# Switches.net
KiCad netlist of a schematic drawn in Altium Designer
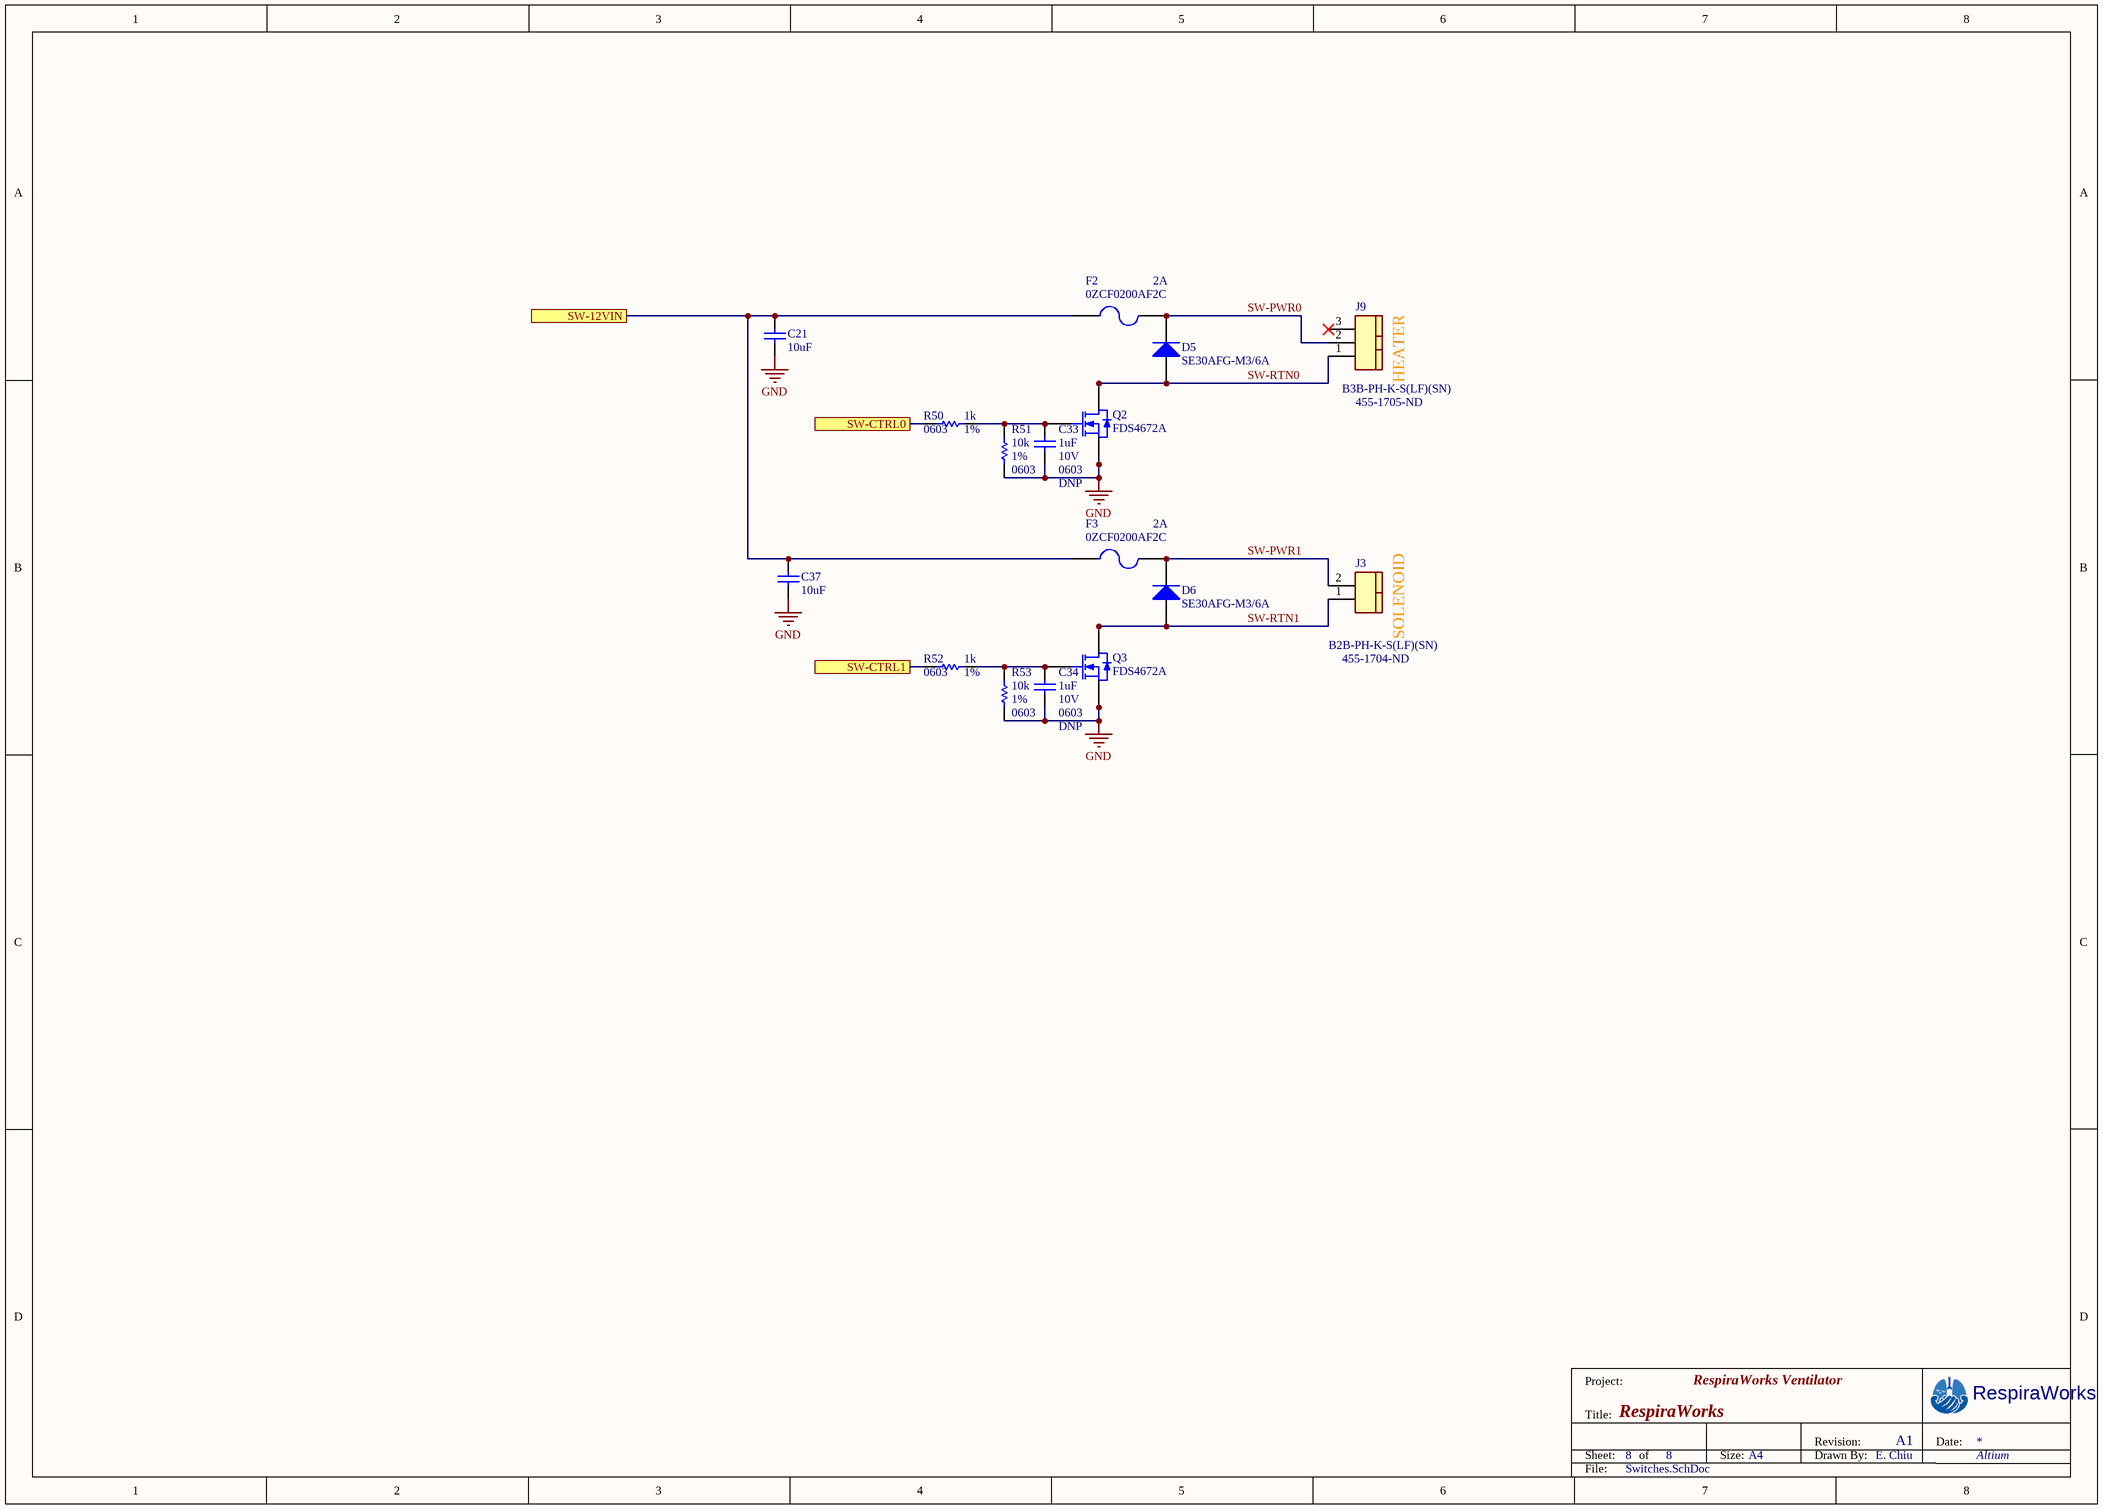
[diagram p0: Switches.SchDoc]

(export (version "E")
  (design (tool "Eeschema 10.0.6"))
  (components
    (comp (ref "C21")
      (value "10uF")
      (footprint "CAP1210")
      (description "Cap 1210")
      (fields (field (name "MANUFACTURER") "Murata") (field (name "VOLTAGE") "25V"))
      (libsource (lib "generic") (part "CAP 1210"))
    )
    (comp (ref "C33")
      (value "1uF")
      (footprint "CAP0603")
      (description "Cap 0603")
      (fields
        (field (name "MANUFACTURER") "Yageo")
        (field (name "VOLTAGE") "10V")
        (field (name "PCB PACKAGE") "0603")
        (field (name "DO NOT POPULATE") "DNP")
        (field (name "Comment") "CAP 0603")
      )
      (libsource (lib "generic") (part "CAP 0603"))
    )
    (comp (ref "C34")
      (value "1uF")
      (footprint "CAP0603")
      (description "Cap 0603")
      (fields
        (field (name "MANUFACTURER") "Yageo")
        (field (name "VOLTAGE") "10V")
        (field (name "PCB PACKAGE") "0603")
        (field (name "DO NOT POPULATE") "DNP")
        (field (name "Comment") "CAP 0603")
      )
      (libsource (lib "generic") (part "CAP 0603"))
    )
    (comp (ref "C37")
      (value "10uF")
      (footprint "CAP1210")
      (description "Cap 1210")
      (fields (field (name "MANUFACTURER") "Murata") (field (name "VOLTAGE") "25V"))
      (libsource (lib "generic") (part "CAP 1210"))
    )
    (comp (ref "D5")
      (value "SE30AFG-M3/6A")
      (footprint "DO-214AC")
      (description "Ultra-Fast Signal Diode, Silicon, 100V, 300mA")
      (fields (field (name "MANUFACTURER") "Vishay") (field (name "MANUFACTURER P/N") "SE30AFG-M3/6A"))
      (libsource (lib "vishay") (part "SE30AFG-M3/6A"))
    )
    (comp (ref "D6")
      (value "SE30AFG-M3/6A")
      (footprint "DO-214AC")
      (description "Ultra-Fast Signal Diode, Silicon, 100V, 300mA")
      (fields (field (name "MANUFACTURER") "Vishay") (field (name "MANUFACTURER P/N") "SE30AFG-M3/6A"))
      (libsource (lib "vishay") (part "SE30AFG-M3/6A"))
    )
    (comp (ref "F2")
      (value "0ZCF0200AF2C")
      (footprint "FUSE2920")
      (description "PTC Fuse, 2A Hold, 24V, 2920 size")
      (fields
        (field (name "MANUFACTURER P/N") "0ZCF0200AF2C")
        (field (name "MANUFACTURER") "Belfuse")
        (field (name "I(HOLD)") "2A")
      )
      (libsource (lib "belfuse") (part "0ZCF0200AF2C"))
    )
    (comp (ref "F3")
      (value "0ZCF0200AF2C")
      (footprint "FUSE2920")
      (description "PTC Fuse, 2A Hold, 24V, 2920 size")
      (fields
        (field (name "MANUFACTURER P/N") "0ZCF0200AF2C")
        (field (name "MANUFACTURER") "Belfuse")
        (field (name "I(HOLD)") "2A")
      )
      (libsource (lib "belfuse") (part "0ZCF0200AF2C"))
    )
    (comp (ref "J3")
      (value "B2B-PH-K-S(LF)(SN)")
      (footprint "JST_B2B-XH-AM")
      (description "CONN HEADER PH TOP 2POS 2MM")
      (fields
        (field (name "MANUFACTURER") "JST Sales America Inc.")
        (field (name "SUPPLIER PART NUMBER 1") "455-1704-ND")
      )
      (libsource (lib "JST XH") (part "B2B-PH-K-S(LF)(SN)"))
    )
    (comp (ref "J9")
      (value "B3B-PH-K-S(LF)(SN)")
      (footprint "JST_B3B-XH-AM")
      (description "CONN HEADER PH TOP 3POS 2MM")
      (fields
        (field (name "MANUFACTURER") "JST Sales America Inc.")
        (field (name "SUPPLIER PART NUMBER 1") "455-1705-ND")
      )
      (libsource (lib "JST XH") (part "B3B-PH-K-S(LF)(SN)"))
    )
    (comp (ref "Q2")
      (value "FDS4672A")
      (footprint "8-SOIC")
      (description "Transistor, BJT NPN, General Purpose 40V")
      (fields (field (name "MANUFACTURER") "On Semi") (field (name "MANUFACTURER P/N") "FDS4672A"))
      (libsource (lib "on-semi") (part "FDS4672A"))
    )
    (comp (ref "Q3")
      (value "FDS4672A")
      (footprint "8-SOIC")
      (description "Transistor, BJT NPN, General Purpose 40V")
      (fields (field (name "MANUFACTURER") "On Semi") (field (name "MANUFACTURER P/N") "FDS4672A"))
      (libsource (lib "on-semi") (part "FDS4672A"))
    )
    (comp (ref "R50")
      (value "1k")
      (footprint "RES0603")
      (description "Res 0603")
      (fields
        (field (name "MANUFACTURER") "Yageo")
        (field (name "PCB PACKAGE") "0603")
        (field (name "TOLERANCE") "1%")
        (field (name "Comment") "RES 0603")
      )
      (libsource (lib "generic") (part "RES 0603"))
    )
    (comp (ref "R51")
      (value "10k")
      (footprint "RES0603")
      (description "Res 0603")
      (fields
        (field (name "MANUFACTURER") "Yageo")
        (field (name "PCB PACKAGE") "0603")
        (field (name "TOLERANCE") "1%")
        (field (name "Comment") "RES 0603")
      )
      (libsource (lib "generic") (part "RES 0603"))
    )
    (comp (ref "R52")
      (value "1k")
      (footprint "RES0603")
      (description "Res 0603")
      (fields
        (field (name "MANUFACTURER") "Yageo")
        (field (name "PCB PACKAGE") "0603")
        (field (name "TOLERANCE") "1%")
        (field (name "Comment") "RES 0603")
      )
      (libsource (lib "generic") (part "RES 0603"))
    )
    (comp (ref "R53")
      (value "10k")
      (footprint "RES0603")
      (description "Res 0603")
      (fields
        (field (name "MANUFACTURER") "Yageo")
        (field (name "PCB PACKAGE") "0603")
        (field (name "TOLERANCE") "1%")
        (field (name "Comment") "RES 0603")
      )
      (libsource (lib "generic") (part "RES 0603"))
    )
  )
  (nets
    (net (code "1") (name "/SW-12VIN") (class "Default")
      (node (ref "C21") (pin "2") (pinfunction "2_2") (pintype "passive"))
      (node (ref "C37") (pin "2") (pinfunction "2_2") (pintype "passive"))
      (node (ref "F2") (pin "1") (pinfunction "1_1") (pintype "passive"))
      (node (ref "F3") (pin "1") (pinfunction "1_1") (pintype "passive"))
    )
    (net (code "2") (name "/SW-CTRL0") (class "Default")
      (node (ref "R50") (pin "2") (pinfunction "2_2") (pintype "passive"))
    )
    (net (code "3") (name "/SW-CTRL1") (class "Default")
      (node (ref "R52") (pin "2") (pinfunction "2_2") (pintype "passive"))
    )
    (net (code "4") (name "/SW-PWR0") (class "Default")
      (node (ref "D5") (pin "K") (pinfunction "K_K") (pintype "passive"))
      (node (ref "F2") (pin "2") (pinfunction "2_2") (pintype "passive"))
      (node (ref "J9") (pin "2") (pinfunction "2_2") (pintype "passive"))
    )
    (net (code "5") (name "/SW-PWR1") (class "Default")
      (node (ref "D6") (pin "K") (pinfunction "K_K") (pintype "passive"))
      (node (ref "F3") (pin "2") (pinfunction "2_2") (pintype "passive"))
      (node (ref "J3") (pin "2") (pinfunction "2_2") (pintype "passive"))
    )
    (net (code "6") (name "/SW-RTN0") (class "Default")
      (node (ref "D5") (pin "A") (pinfunction "A_A") (pintype "passive"))
      (node (ref "J9") (pin "1") (pinfunction "1_1") (pintype "passive"))
      (node (ref "Q2") (pin "5") (pinfunction "D_5") (pintype "passive"))
      (node (ref "Q2") (pin "6") (pinfunction "D_6") (pintype "passive"))
      (node (ref "Q2") (pin "7") (pinfunction "D_7") (pintype "passive"))
      (node (ref "Q2") (pin "8") (pinfunction "D_8") (pintype "passive"))
    )
    (net (code "7") (name "/SW-RTN1") (class "Default")
      (node (ref "D6") (pin "A") (pinfunction "A_A") (pintype "passive"))
      (node (ref "J3") (pin "1") (pinfunction "1_1") (pintype "passive"))
      (node (ref "Q3") (pin "5") (pinfunction "D_5") (pintype "passive"))
      (node (ref "Q3") (pin "6") (pinfunction "D_6") (pintype "passive"))
      (node (ref "Q3") (pin "7") (pinfunction "D_7") (pintype "passive"))
      (node (ref "Q3") (pin "8") (pinfunction "D_8") (pintype "passive"))
    )
    (net (code "8") (name "GND") (class "Default")
      (node (ref "C21") (pin "1") (pinfunction "1_1") (pintype "passive"))
      (node (ref "C33") (pin "2") (pinfunction "2_2") (pintype "passive"))
      (node (ref "C34") (pin "2") (pinfunction "2_2") (pintype "passive"))
      (node (ref "C37") (pin "1") (pinfunction "1_1") (pintype "passive"))
      (node (ref "Q2") (pin "1") (pinfunction "S_1") (pintype "passive"))
      (node (ref "Q2") (pin "2") (pinfunction "S_2") (pintype "passive"))
      (node (ref "Q2") (pin "3") (pinfunction "S_3") (pintype "passive"))
      (node (ref "Q3") (pin "1") (pinfunction "S_1") (pintype "passive"))
      (node (ref "Q3") (pin "2") (pinfunction "S_2") (pintype "passive"))
      (node (ref "Q3") (pin "3") (pinfunction "S_3") (pintype "passive"))
      (node (ref "R51") (pin "2") (pinfunction "2_2") (pintype "passive"))
      (node (ref "R53") (pin "2") (pinfunction "2_2") (pintype "passive"))
    )
    (net (code "9") (name "Net-(Q2-G)") (class "Default")
      (node (ref "C33") (pin "1") (pinfunction "1_1") (pintype "passive"))
      (node (ref "Q2") (pin "4") (pinfunction "G_4") (pintype "passive"))
      (node (ref "R50") (pin "1") (pinfunction "1_1") (pintype "passive"))
      (node (ref "R51") (pin "1") (pinfunction "1_1") (pintype "passive"))
    )
    (net (code "10") (name "Net-(Q3-G)") (class "Default")
      (node (ref "C34") (pin "1") (pinfunction "1_1") (pintype "passive"))
      (node (ref "Q3") (pin "4") (pinfunction "G_4") (pintype "passive"))
      (node (ref "R52") (pin "1") (pinfunction "1_1") (pintype "passive"))
      (node (ref "R53") (pin "1") (pinfunction "1_1") (pintype "passive"))
    )
    (net (code "11") (name "unconnected-(J9-Pad3)") (class "Default")
      (node (ref "J9") (pin "3") (pinfunction "3_3") (pintype "passive+no_connect"))
    )
  )
)
